# LED_Cube_8x8x8_Nano.net
KiCad netlist of a schematic drawn in EasyEDA
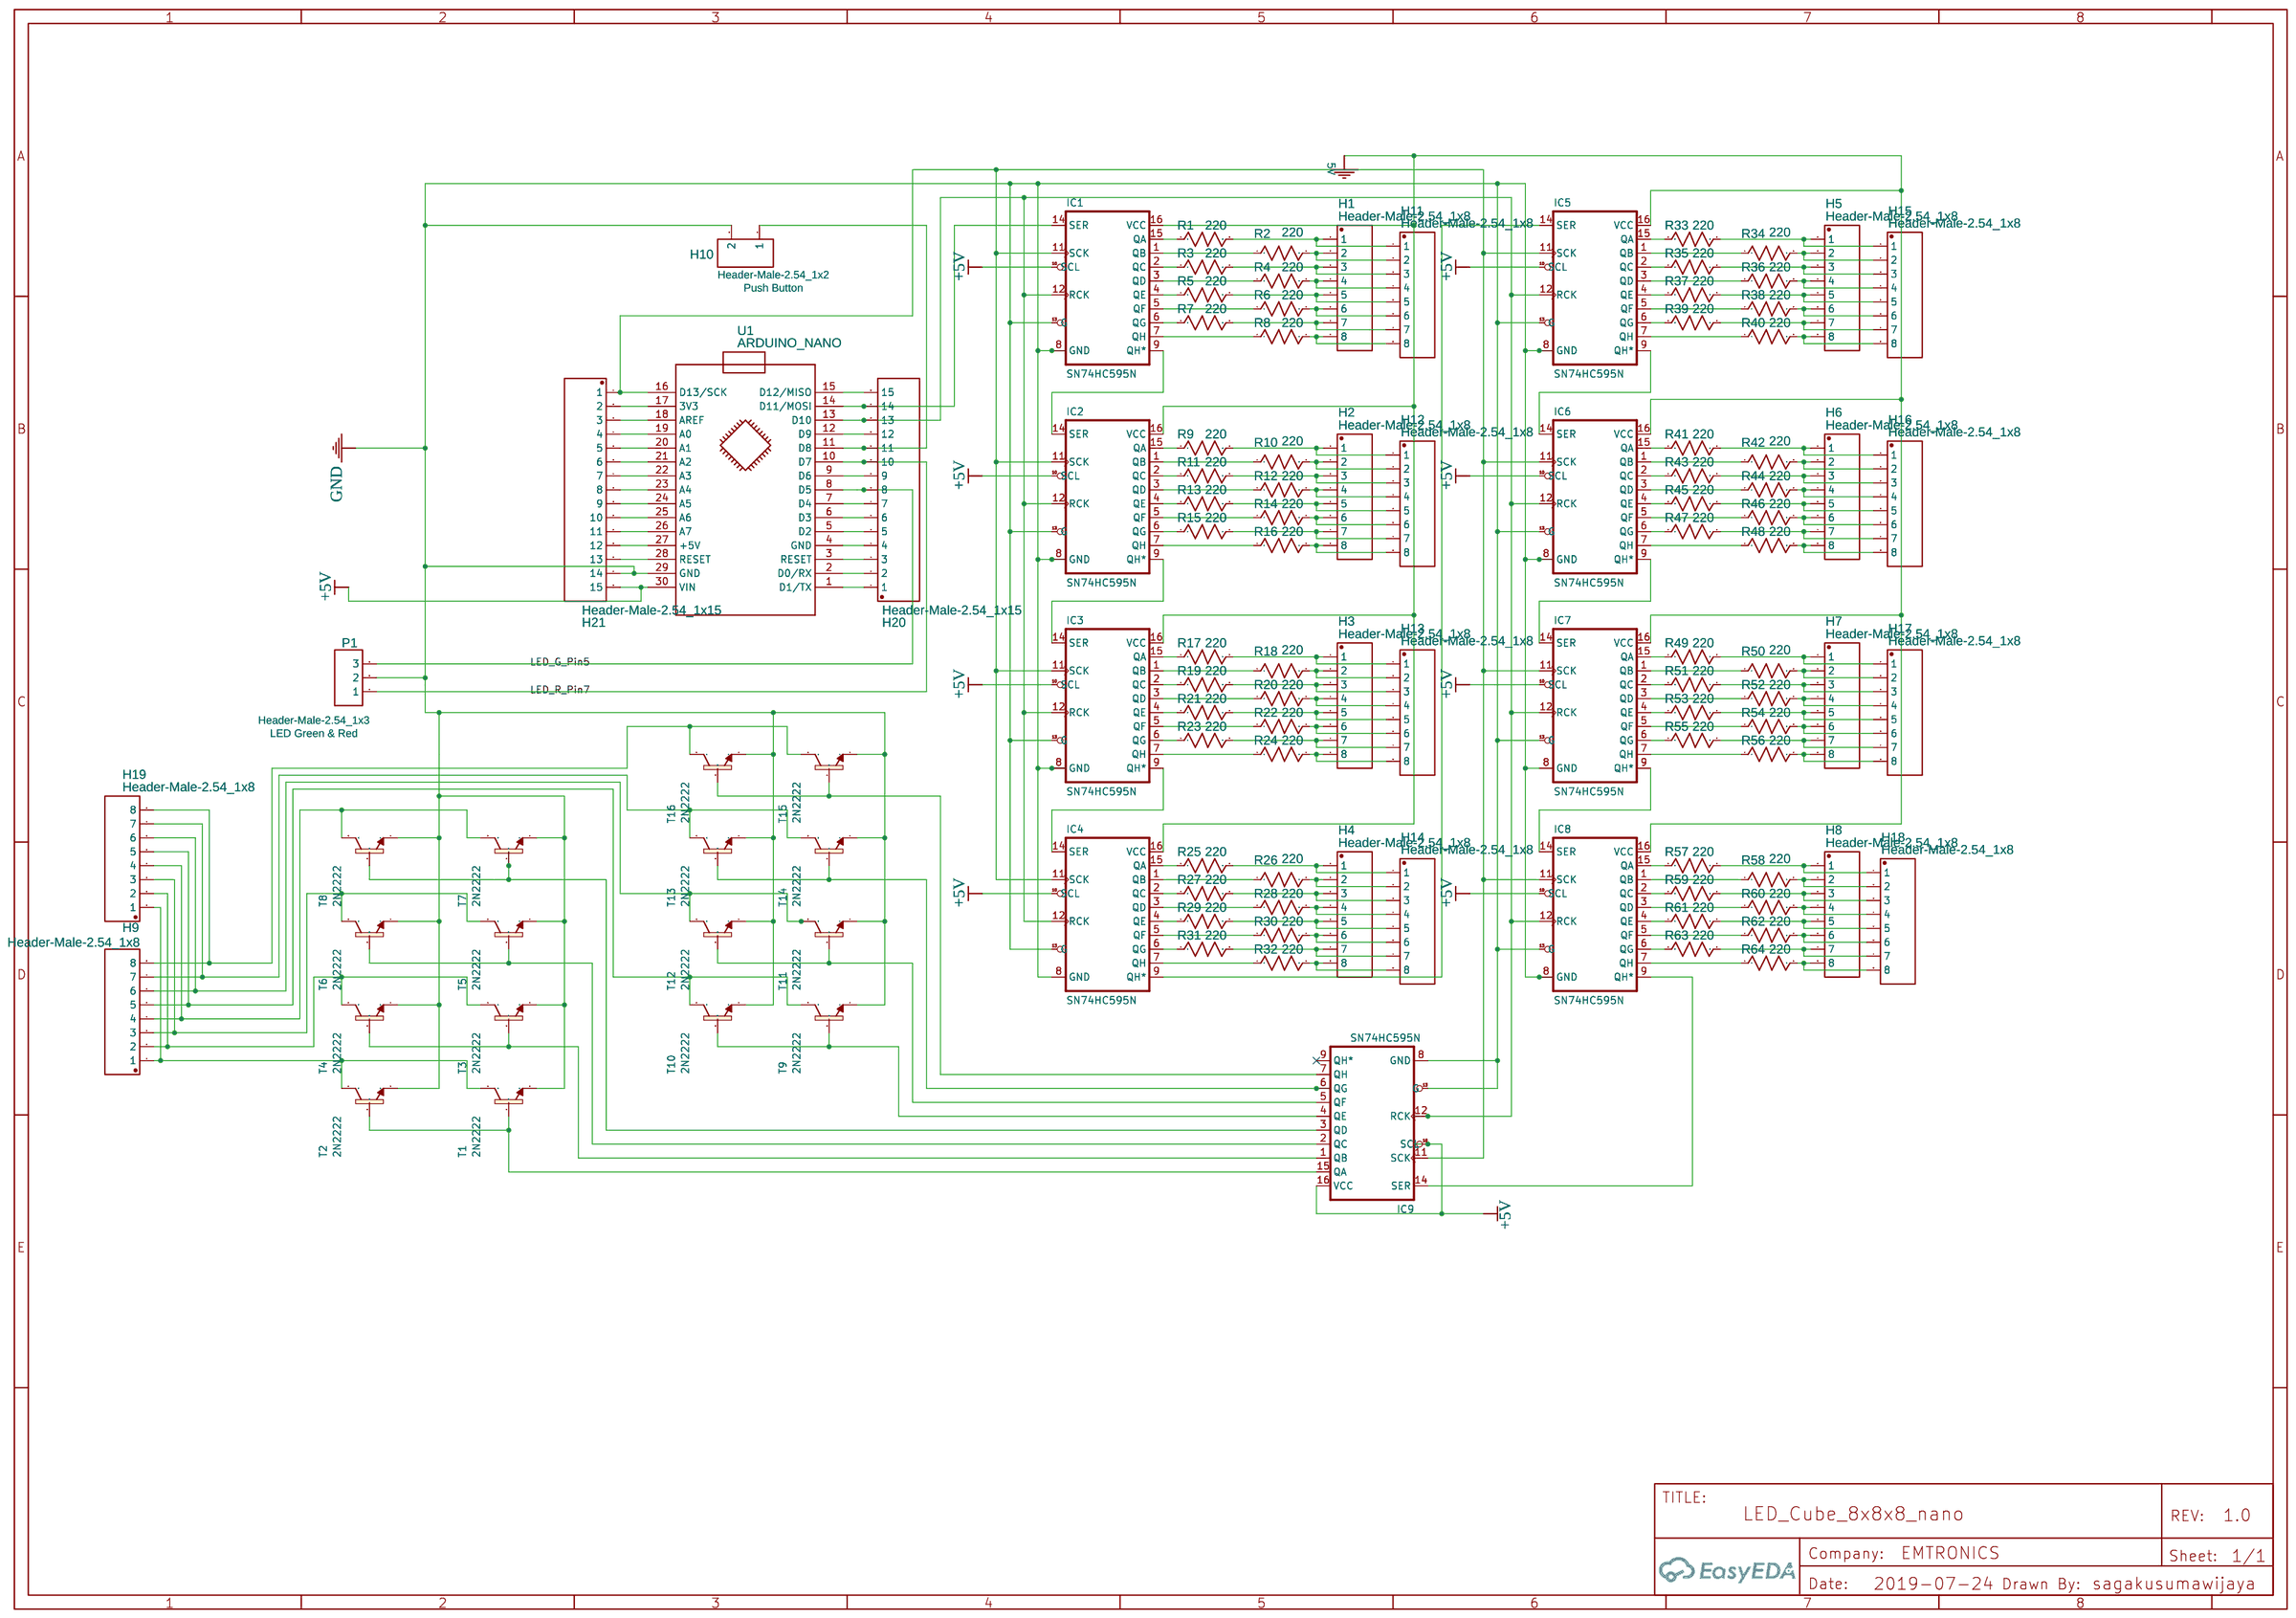
[diagram p0: schematic sheet]

(export (version "E")
  (design (tool "Eeschema 10.0.6"))
  (components
    (comp (ref "H1")
      (value "Header-Male-2.54_1x8")
      (fields
        (field (name "BOM_Manufacturer Part") "210S-1*8P L=11.6MMGold-plated black")
        (field (name "BOM_Supplier Part") "C124381")
      )
      (libsource (lib "") (part "Unknown_960_200"))
    )
    (comp (ref "H2")
      (value "Header-Male-2.54_1x8")
      (fields
        (field (name "BOM_Manufacturer Part") "210S-1*8P L=11.6MMGold-plated black")
        (field (name "BOM_Supplier Part") "C124381")
      )
      (libsource (lib "") (part "Unknown_960_350"))
    )
    (comp (ref "H3")
      (value "Header-Male-2.54_1x8")
      (fields
        (field (name "BOM_Manufacturer Part") "210S-1*8P L=11.6MMGold-plated black")
        (field (name "BOM_Supplier Part") "C124381")
      )
      (libsource (lib "") (part "Unknown_960_500"))
    )
    (comp (ref "H4")
      (value "Header-Male-2.54_1x8")
      (fields
        (field (name "BOM_Manufacturer Part") "210S-1*8P L=11.6MMGold-plated black")
        (field (name "BOM_Supplier Part") "C124381")
      )
      (libsource (lib "") (part "Unknown_960_650"))
    )
    (comp (ref "H5")
      (value "Header-Male-2.54_1x8")
      (fields
        (field (name "BOM_Manufacturer Part") "210S-1*8P L=11.6MMGold-plated black")
        (field (name "BOM_Supplier Part") "C124381")
      )
      (libsource (lib "") (part "Unknown_1310_200"))
    )
    (comp (ref "H6")
      (value "Header-Male-2.54_1x8")
      (fields
        (field (name "BOM_Manufacturer Part") "210S-1*8P L=11.6MMGold-plated black")
        (field (name "BOM_Supplier Part") "C124381")
      )
      (libsource (lib "") (part "Unknown_1310_350"))
    )
    (comp (ref "H7")
      (value "Header-Male-2.54_1x8")
      (fields
        (field (name "BOM_Manufacturer Part") "210S-1*8P L=11.6MMGold-plated black")
        (field (name "BOM_Supplier Part") "C124381")
      )
      (libsource (lib "") (part "Unknown_1310_500"))
    )
    (comp (ref "H8")
      (value "Header-Male-2.54_1x8")
      (fields
        (field (name "BOM_Manufacturer Part") "210S-1*8P L=11.6MMGold-plated black")
        (field (name "BOM_Supplier Part") "C124381")
      )
      (libsource (lib "") (part "Unknown_1310_650"))
    )
    (comp (ref "H9")
      (value "Header-Male-2.54_1x8")
      (fields
        (field (name "BOM_Manufacturer Part") "210S-1*8P L=11.6MMGold-plated black")
        (field (name "BOM_Supplier Part") "C124381")
      )
      (libsource (lib "") (part "Unknown_80_720"))
    )
    (comp (ref "H10")
      (value "Header-Male-2.54_1x2\\nPush Button")
      (fields (field (name "BOM_Manufacturer Part") "826629-2") (field (name "BOM_Supplier Part") "C86471"))
      (libsource (lib "") (part "Unknown_525_170"))
    )
    (comp (ref "H11")
      (value "Header-Male-2.54_1x8")
      (fields
        (field (name "BOM_Manufacturer Part") "210S-1*8P L=11.6MMGold-plated black")
        (field (name "BOM_Supplier Part") "C124381")
      )
      (libsource (lib "") (part "Unknown_1005_205"))
    )
    (comp (ref "H12")
      (value "Header-Male-2.54_1x8")
      (fields
        (field (name "BOM_Manufacturer Part") "210S-1*8P L=11.6MMGold-plated black")
        (field (name "BOM_Supplier Part") "C124381")
      )
      (libsource (lib "") (part "Unknown_1005_355"))
    )
    (comp (ref "H13")
      (value "Header-Male-2.54_1x8")
      (fields
        (field (name "BOM_Manufacturer Part") "210S-1*8P L=11.6MMGold-plated black")
        (field (name "BOM_Supplier Part") "C124381")
      )
      (libsource (lib "") (part "Unknown_1005_505"))
    )
    (comp (ref "H14")
      (value "Header-Male-2.54_1x8")
      (fields
        (field (name "BOM_Manufacturer Part") "210S-1*8P L=11.6MMGold-plated black")
        (field (name "BOM_Supplier Part") "C124381")
      )
      (libsource (lib "") (part "Unknown_1005_655"))
    )
    (comp (ref "H15")
      (value "Header-Male-2.54_1x8")
      (fields
        (field (name "BOM_Manufacturer Part") "210S-1*8P L=11.6MMGold-plated black")
        (field (name "BOM_Supplier Part") "C124381")
      )
      (libsource (lib "") (part "Unknown_1355_205"))
    )
    (comp (ref "H16")
      (value "Header-Male-2.54_1x8")
      (fields
        (field (name "BOM_Manufacturer Part") "210S-1*8P L=11.6MMGold-plated black")
        (field (name "BOM_Supplier Part") "C124381")
      )
      (libsource (lib "") (part "Unknown_1355_355"))
    )
    (comp (ref "H17")
      (value "Header-Male-2.54_1x8")
      (fields
        (field (name "BOM_Manufacturer Part") "210S-1*8P L=11.6MMGold-plated black")
        (field (name "BOM_Supplier Part") "C124381")
      )
      (libsource (lib "") (part "Unknown_1355_505"))
    )
    (comp (ref "H18")
      (value "Header-Male-2.54_1x8")
      (fields
        (field (name "BOM_Manufacturer Part") "210S-1*8P L=11.6MMGold-plated black")
        (field (name "BOM_Supplier Part") "C124381")
      )
      (libsource (lib "") (part "Unknown_1350_655"))
    )
    (comp (ref "H19")
      (value "Header-Male-2.54_1x8")
      (fields
        (field (name "BOM_Manufacturer Part") "210S-1*8P L=11.6MMGold-plated black")
        (field (name "BOM_Supplier Part") "C124381")
      )
      (libsource (lib "") (part "Unknown_80_610"))
    )
    (comp (ref "H20")
      (value "Header-Male-2.54_1x15")
      (fields
        (field (name "BOM_Manufacturer Part") "210S-1*15P L=11.6MMGold-plated black")
        (field (name "BOM_Supplier Part") "C124373")
      )
      (libsource (lib "") (part "Unknown_630_340"))
    )
    (comp (ref "H21")
      (value "Header-Male-2.54_1x15")
      (fields
        (field (name "BOM_Manufacturer Part") "210S-1*15P L=11.6MMGold-plated black")
        (field (name "BOM_Supplier Part") "C124373")
      )
      (libsource (lib "") (part "Unknown_415_350"))
    )
    (comp (ref "IC1") (value "SN74HC595N") (libsource (lib "") (part "Unknown_775_195")))
    (comp (ref "IC2") (value "SN74HC595N") (libsource (lib "") (part "Unknown_775_345")))
    (comp (ref "IC3") (value "SN74HC595N") (libsource (lib "") (part "Unknown_775_495")))
    (comp (ref "IC4") (value "SN74HC595N") (libsource (lib "") (part "Unknown_775_645")))
    (comp (ref "IC5") (value "SN74HC595N") (libsource (lib "") (part "Unknown_1125_195")))
    (comp (ref "IC6") (value "SN74HC595N") (libsource (lib "") (part "Unknown_1125_345")))
    (comp (ref "IC7") (value "SN74HC595N") (libsource (lib "") (part "Unknown_1125_495")))
    (comp (ref "IC8") (value "SN74HC595N") (libsource (lib "") (part "Unknown_1125_645")))
    (comp (ref "IC9") (value "SN74HC595N") (libsource (lib "") (part "Unknown_985_805")))
    (comp (ref "P1")
      (value "Header-Male-2.54_1x3\\nLED Green & Red")
      (fields
        (field (name "BOM_Manufacturer Part") "Header2.54mm 1*3P")
        (field (name "BOM_Supplier Part") "C49257")
      )
      (libsource (lib "") (part "Unknown_245_480"))
    )
    (comp (ref "R1")
      (value "220")
      (fields (field (name "BOM_Manufacturer Part") "?"))
      (libsource (lib "") (part "Res_AXIAL-0.4(1/4W)_US"))
    )
    (comp (ref "R2")
      (value "220")
      (fields (field (name "BOM_Manufacturer Part") "?"))
      (libsource (lib "") (part "Res_AXIAL-0.4(1/4W)_US"))
    )
    (comp (ref "R3")
      (value "220")
      (fields (field (name "BOM_Manufacturer Part") "?"))
      (libsource (lib "") (part "Res_AXIAL-0.4(1/4W)_US"))
    )
    (comp (ref "R4")
      (value "220")
      (fields (field (name "BOM_Manufacturer Part") "?"))
      (libsource (lib "") (part "Res_AXIAL-0.4(1/4W)_US"))
    )
    (comp (ref "R5")
      (value "220")
      (fields (field (name "BOM_Manufacturer Part") "?"))
      (libsource (lib "") (part "Res_AXIAL-0.4(1/4W)_US"))
    )
    (comp (ref "R6")
      (value "220")
      (fields (field (name "BOM_Manufacturer Part") "?"))
      (libsource (lib "") (part "Res_AXIAL-0.4(1/4W)_US"))
    )
    (comp (ref "R7")
      (value "220")
      (fields (field (name "BOM_Manufacturer Part") "?"))
      (libsource (lib "") (part "Res_AXIAL-0.4(1/4W)_US"))
    )
    (comp (ref "R8")
      (value "220")
      (fields (field (name "BOM_Manufacturer Part") "?"))
      (libsource (lib "") (part "Res_AXIAL-0.4(1/4W)_US"))
    )
    (comp (ref "R9")
      (value "220")
      (fields (field (name "BOM_Manufacturer Part") "?"))
      (libsource (lib "") (part "Res_AXIAL-0.4(1/4W)_US"))
    )
    (comp (ref "R10")
      (value "220")
      (fields (field (name "BOM_Manufacturer Part") "?"))
      (libsource (lib "") (part "Res_AXIAL-0.4(1/4W)_US"))
    )
    (comp (ref "R11")
      (value "220")
      (fields (field (name "BOM_Manufacturer Part") "?"))
      (libsource (lib "") (part "Res_AXIAL-0.4(1/4W)_US"))
    )
    (comp (ref "R12")
      (value "220")
      (fields (field (name "BOM_Manufacturer Part") "?"))
      (libsource (lib "") (part "Res_AXIAL-0.4(1/4W)_US"))
    )
    (comp (ref "R13")
      (value "220")
      (fields (field (name "BOM_Manufacturer Part") "?"))
      (libsource (lib "") (part "Res_AXIAL-0.4(1/4W)_US"))
    )
    (comp (ref "R14")
      (value "220")
      (fields (field (name "BOM_Manufacturer Part") "?"))
      (libsource (lib "") (part "Res_AXIAL-0.4(1/4W)_US"))
    )
    (comp (ref "R15")
      (value "220")
      (fields (field (name "BOM_Manufacturer Part") "?"))
      (libsource (lib "") (part "Res_AXIAL-0.4(1/4W)_US"))
    )
    (comp (ref "R16")
      (value "220")
      (fields (field (name "BOM_Manufacturer Part") "?"))
      (libsource (lib "") (part "Res_AXIAL-0.4(1/4W)_US"))
    )
    (comp (ref "R17")
      (value "220")
      (fields (field (name "BOM_Manufacturer Part") "?"))
      (libsource (lib "") (part "Res_AXIAL-0.4(1/4W)_US"))
    )
    (comp (ref "R18")
      (value "220")
      (fields (field (name "BOM_Manufacturer Part") "?"))
      (libsource (lib "") (part "Res_AXIAL-0.4(1/4W)_US"))
    )
    (comp (ref "R19")
      (value "220")
      (fields (field (name "BOM_Manufacturer Part") "?"))
      (libsource (lib "") (part "Res_AXIAL-0.4(1/4W)_US"))
    )
    (comp (ref "R20")
      (value "220")
      (fields (field (name "BOM_Manufacturer Part") "?"))
      (libsource (lib "") (part "Res_AXIAL-0.4(1/4W)_US"))
    )
    (comp (ref "R21")
      (value "220")
      (fields (field (name "BOM_Manufacturer Part") "?"))
      (libsource (lib "") (part "Res_AXIAL-0.4(1/4W)_US"))
    )
    (comp (ref "R22")
      (value "220")
      (fields (field (name "BOM_Manufacturer Part") "?"))
      (libsource (lib "") (part "Res_AXIAL-0.4(1/4W)_US"))
    )
    (comp (ref "R23")
      (value "220")
      (fields (field (name "BOM_Manufacturer Part") "?"))
      (libsource (lib "") (part "Res_AXIAL-0.4(1/4W)_US"))
    )
    (comp (ref "R24")
      (value "220")
      (fields (field (name "BOM_Manufacturer Part") "?"))
      (libsource (lib "") (part "Res_AXIAL-0.4(1/4W)_US"))
    )
    (comp (ref "R25")
      (value "220")
      (fields (field (name "BOM_Manufacturer Part") "?"))
      (libsource (lib "") (part "Res_AXIAL-0.4(1/4W)_US"))
    )
    (comp (ref "R26")
      (value "220")
      (fields (field (name "BOM_Manufacturer Part") "?"))
      (libsource (lib "") (part "Res_AXIAL-0.4(1/4W)_US"))
    )
    (comp (ref "R27")
      (value "220")
      (fields (field (name "BOM_Manufacturer Part") "?"))
      (libsource (lib "") (part "Res_AXIAL-0.4(1/4W)_US"))
    )
    (comp (ref "R28")
      (value "220")
      (fields (field (name "BOM_Manufacturer Part") "?"))
      (libsource (lib "") (part "Res_AXIAL-0.4(1/4W)_US"))
    )
    (comp (ref "R29")
      (value "220")
      (fields (field (name "BOM_Manufacturer Part") "?"))
      (libsource (lib "") (part "Res_AXIAL-0.4(1/4W)_US"))
    )
    (comp (ref "R30")
      (value "220")
      (fields (field (name "BOM_Manufacturer Part") "?"))
      (libsource (lib "") (part "Res_AXIAL-0.4(1/4W)_US"))
    )
    (comp (ref "R31")
      (value "220")
      (fields (field (name "BOM_Manufacturer Part") "?"))
      (libsource (lib "") (part "Res_AXIAL-0.4(1/4W)_US"))
    )
    (comp (ref "R32")
      (value "220")
      (fields (field (name "BOM_Manufacturer Part") "?"))
      (libsource (lib "") (part "Res_AXIAL-0.4(1/4W)_US"))
    )
    (comp (ref "R33")
      (value "220")
      (fields (field (name "BOM_Manufacturer Part") "?"))
      (libsource (lib "") (part "Res_AXIAL-0.4(1/4W)_US"))
    )
    (comp (ref "R34")
      (value "220")
      (fields (field (name "BOM_Manufacturer Part") "?"))
      (libsource (lib "") (part "Res_AXIAL-0.4(1/4W)_US"))
    )
    (comp (ref "R35")
      (value "220")
      (fields (field (name "BOM_Manufacturer Part") "?"))
      (libsource (lib "") (part "Res_AXIAL-0.4(1/4W)_US"))
    )
    (comp (ref "R36")
      (value "220")
      (fields (field (name "BOM_Manufacturer Part") "?"))
      (libsource (lib "") (part "Res_AXIAL-0.4(1/4W)_US"))
    )
    (comp (ref "R37")
      (value "220")
      (fields (field (name "BOM_Manufacturer Part") "?"))
      (libsource (lib "") (part "Res_AXIAL-0.4(1/4W)_US"))
    )
    (comp (ref "R38")
      (value "220")
      (fields (field (name "BOM_Manufacturer Part") "?"))
      (libsource (lib "") (part "Res_AXIAL-0.4(1/4W)_US"))
    )
    (comp (ref "R39")
      (value "220")
      (fields (field (name "BOM_Manufacturer Part") "?"))
      (libsource (lib "") (part "Res_AXIAL-0.4(1/4W)_US"))
    )
    (comp (ref "R40")
      (value "220")
      (fields (field (name "BOM_Manufacturer Part") "?"))
      (libsource (lib "") (part "Res_AXIAL-0.4(1/4W)_US"))
    )
    (comp (ref "R41")
      (value "220")
      (fields (field (name "BOM_Manufacturer Part") "?"))
      (libsource (lib "") (part "Res_AXIAL-0.4(1/4W)_US"))
    )
    (comp (ref "R42")
      (value "220")
      (fields (field (name "BOM_Manufacturer Part") "?"))
      (libsource (lib "") (part "Res_AXIAL-0.4(1/4W)_US"))
    )
    (comp (ref "R43")
      (value "220")
      (fields (field (name "BOM_Manufacturer Part") "?"))
      (libsource (lib "") (part "Res_AXIAL-0.4(1/4W)_US"))
    )
    (comp (ref "R44")
      (value "220")
      (fields (field (name "BOM_Manufacturer Part") "?"))
      (libsource (lib "") (part "Res_AXIAL-0.4(1/4W)_US"))
    )
    (comp (ref "R45")
      (value "220")
      (fields (field (name "BOM_Manufacturer Part") "?"))
      (libsource (lib "") (part "Res_AXIAL-0.4(1/4W)_US"))
    )
    (comp (ref "R46")
      (value "220")
      (fields (field (name "BOM_Manufacturer Part") "?"))
      (libsource (lib "") (part "Res_AXIAL-0.4(1/4W)_US"))
    )
    (comp (ref "R47")
      (value "220")
      (fields (field (name "BOM_Manufacturer Part") "?"))
      (libsource (lib "") (part "Res_AXIAL-0.4(1/4W)_US"))
    )
    (comp (ref "R48")
      (value "220")
      (fields (field (name "BOM_Manufacturer Part") "?"))
      (libsource (lib "") (part "Res_AXIAL-0.4(1/4W)_US"))
    )
    (comp (ref "R49")
      (value "220")
      (fields (field (name "BOM_Manufacturer Part") "?"))
      (libsource (lib "") (part "Res_AXIAL-0.4(1/4W)_US"))
    )
    (comp (ref "R50")
      (value "220")
      (fields (field (name "BOM_Manufacturer Part") "?"))
      (libsource (lib "") (part "Res_AXIAL-0.4(1/4W)_US"))
    )
    (comp (ref "R51")
      (value "220")
      (fields (field (name "BOM_Manufacturer Part") "?"))
      (libsource (lib "") (part "Res_AXIAL-0.4(1/4W)_US"))
    )
    (comp (ref "R52")
      (value "220")
      (fields (field (name "BOM_Manufacturer Part") "?"))
      (libsource (lib "") (part "Res_AXIAL-0.4(1/4W)_US"))
    )
    (comp (ref "R53")
      (value "220")
      (fields (field (name "BOM_Manufacturer Part") "?"))
      (libsource (lib "") (part "Res_AXIAL-0.4(1/4W)_US"))
    )
    (comp (ref "R54")
      (value "220")
      (fields (field (name "BOM_Manufacturer Part") "?"))
      (libsource (lib "") (part "Res_AXIAL-0.4(1/4W)_US"))
    )
    (comp (ref "R55")
      (value "220")
      (fields (field (name "BOM_Manufacturer Part") "?"))
      (libsource (lib "") (part "Res_AXIAL-0.4(1/4W)_US"))
    )
    (comp (ref "R56")
      (value "220")
      (fields (field (name "BOM_Manufacturer Part") "?"))
      (libsource (lib "") (part "Res_AXIAL-0.4(1/4W)_US"))
    )
    (comp (ref "R57")
      (value "220")
      (fields (field (name "BOM_Manufacturer Part") "?"))
      (libsource (lib "") (part "Res_AXIAL-0.4(1/4W)_US"))
    )
    (comp (ref "R58")
      (value "220")
      (fields (field (name "BOM_Manufacturer Part") "?"))
      (libsource (lib "") (part "Res_AXIAL-0.4(1/4W)_US"))
    )
    (comp (ref "R59")
      (value "220")
      (fields (field (name "BOM_Manufacturer Part") "?"))
      (libsource (lib "") (part "Res_AXIAL-0.4(1/4W)_US"))
    )
    (comp (ref "R60")
      (value "220")
      (fields (field (name "BOM_Manufacturer Part") "?"))
      (libsource (lib "") (part "Res_AXIAL-0.4(1/4W)_US"))
    )
    (comp (ref "R61")
      (value "220")
      (fields (field (name "BOM_Manufacturer Part") "?"))
      (libsource (lib "") (part "Res_AXIAL-0.4(1/4W)_US"))
    )
    (comp (ref "R62")
      (value "220")
      (fields (field (name "BOM_Manufacturer Part") "?"))
      (libsource (lib "") (part "Res_AXIAL-0.4(1/4W)_US"))
    )
    (comp (ref "R63")
      (value "220")
      (fields (field (name "BOM_Manufacturer Part") "?"))
      (libsource (lib "") (part "Res_AXIAL-0.4(1/4W)_US"))
    )
    (comp (ref "R64")
      (value "220")
      (fields (field (name "BOM_Manufacturer Part") "?"))
      (libsource (lib "") (part "Res_AXIAL-0.4(1/4W)_US"))
    )
    (comp (ref "T1") (value "2N2222") (libsource (lib "") (part "Unknown_355_785")))
    (comp (ref "T2") (value "2N2222") (libsource (lib "") (part "Unknown_255_785")))
    (comp (ref "T3") (value "2N2222") (libsource (lib "") (part "Unknown_355_725")))
    (comp (ref "T4") (value "2N2222") (libsource (lib "") (part "Unknown_255_725")))
    (comp (ref "T5") (value "2N2222") (libsource (lib "") (part "Unknown_355_665")))
    (comp (ref "T6") (value "2N2222") (libsource (lib "") (part "Unknown_255_665")))
    (comp (ref "T7") (value "2N2222") (libsource (lib "") (part "Unknown_355_605")))
    (comp (ref "T8") (value "2N2222") (libsource (lib "") (part "Unknown_255_605")))
    (comp (ref "T9") (value "2N2222") (libsource (lib "") (part "Unknown_585_725")))
    (comp (ref "T10") (value "2N2222") (libsource (lib "") (part "Unknown_505_725")))
    (comp (ref "T11") (value "2N2222") (libsource (lib "") (part "Unknown_585_665")))
    (comp (ref "T12") (value "2N2222") (libsource (lib "") (part "Unknown_505_665")))
    (comp (ref "T13") (value "2N2222") (libsource (lib "") (part "Unknown_505_605")))
    (comp (ref "T14") (value "2N2222") (libsource (lib "") (part "Unknown_585_605")))
    (comp (ref "T15") (value "2N2222") (libsource (lib "") (part "Unknown_585_545")))
    (comp (ref "T16") (value "2N2222") (libsource (lib "") (part "Unknown_505_545")))
    (comp (ref "U1")
      (value "ARDUINO_NANO")
      (fields (field (name "BOM_Manufacturer Part") "?"))
      (libsource (lib "") (part "Unknown_525_340"))
    )
  )
  (nets
    (net (code "1") (name "+5V") (class "Default")
      (node (ref "H21") (pin "15") (pinfunction "15_15") (pintype "unspecified"))
      (node (ref "IC1") (pin "10") (pinfunction "SCL_10") (pintype "bidirectional"))
      (node (ref "IC2") (pin "10") (pinfunction "SCL_10") (pintype "bidirectional"))
      (node (ref "IC3") (pin "10") (pinfunction "SCL_10") (pintype "bidirectional"))
      (node (ref "IC4") (pin "10") (pinfunction "SCL_10") (pintype "bidirectional"))
      (node (ref "IC5") (pin "10") (pinfunction "SCL_10") (pintype "bidirectional"))
      (node (ref "IC6") (pin "10") (pinfunction "SCL_10") (pintype "bidirectional"))
      (node (ref "IC7") (pin "10") (pinfunction "SCL_10") (pintype "bidirectional"))
      (node (ref "IC8") (pin "10") (pinfunction "SCL_10") (pintype "bidirectional"))
      (node (ref "IC9") (pin "10") (pinfunction "SCL_10") (pintype "bidirectional"))
      (node (ref "IC9") (pin "16") (pinfunction "VCC_16") (pintype "bidirectional"))
      (node (ref "U1") (pin "30") (pinfunction "VIN_30") (pintype "unspecified"))
    )
    (net (code "2") (name "/LED_G_Pin5") (class "Default")
      (node (ref "H20") (pin "8") (pinfunction "8_8") (pintype "unspecified"))
      (node (ref "P1") (pin "3") (pinfunction "3_3") (pintype "input"))
      (node (ref "U1") (pin "8") (pinfunction "D5_8") (pintype "unspecified"))
    )
    (net (code "3") (name "/LED_R_Pin7") (class "Default")
      (node (ref "H20") (pin "10") (pinfunction "10_10") (pintype "unspecified"))
      (node (ref "P1") (pin "1") (pinfunction "1_1") (pintype "input"))
      (node (ref "U1") (pin "10") (pinfunction "D7_10") (pintype "unspecified"))
    )
    (net (code "4") (name "5V") (class "Default")
      (node (ref "IC1") (pin "16") (pinfunction "VCC_16") (pintype "bidirectional"))
      (node (ref "IC2") (pin "16") (pinfunction "VCC_16") (pintype "bidirectional"))
      (node (ref "IC3") (pin "16") (pinfunction "VCC_16") (pintype "bidirectional"))
      (node (ref "IC4") (pin "16") (pinfunction "VCC_16") (pintype "bidirectional"))
      (node (ref "IC5") (pin "16") (pinfunction "VCC_16") (pintype "bidirectional"))
      (node (ref "IC6") (pin "16") (pinfunction "VCC_16") (pintype "bidirectional"))
      (node (ref "IC7") (pin "16") (pinfunction "VCC_16") (pintype "bidirectional"))
      (node (ref "IC8") (pin "16") (pinfunction "VCC_16") (pintype "bidirectional"))
    )
    (net (code "5") (name "GND") (class "Default")
      (node (ref "H10") (pin "2") (pinfunction "2_2") (pintype "unspecified"))
      (node (ref "H21") (pin "14") (pinfunction "14_14") (pintype "unspecified"))
      (node (ref "IC1") (pin "13") (pinfunction "G_13") (pintype "bidirectional"))
      (node (ref "IC1") (pin "8") (pinfunction "GND_8") (pintype "bidirectional"))
      (node (ref "IC2") (pin "13") (pinfunction "G_13") (pintype "bidirectional"))
      (node (ref "IC2") (pin "8") (pinfunction "GND_8") (pintype "bidirectional"))
      (node (ref "IC3") (pin "13") (pinfunction "G_13") (pintype "bidirectional"))
      (node (ref "IC3") (pin "8") (pinfunction "GND_8") (pintype "bidirectional"))
      (node (ref "IC4") (pin "13") (pinfunction "G_13") (pintype "bidirectional"))
      (node (ref "IC4") (pin "8") (pinfunction "GND_8") (pintype "bidirectional"))
      (node (ref "IC5") (pin "13") (pinfunction "G_13") (pintype "bidirectional"))
      (node (ref "IC5") (pin "8") (pinfunction "GND_8") (pintype "bidirectional"))
      (node (ref "IC6") (pin "13") (pinfunction "G_13") (pintype "bidirectional"))
      (node (ref "IC6") (pin "8") (pinfunction "GND_8") (pintype "bidirectional"))
      (node (ref "IC7") (pin "13") (pinfunction "G_13") (pintype "bidirectional"))
      (node (ref "IC7") (pin "8") (pinfunction "GND_8") (pintype "bidirectional"))
      (node (ref "IC8") (pin "13") (pinfunction "G_13") (pintype "bidirectional"))
      (node (ref "IC8") (pin "8") (pinfunction "GND_8") (pintype "bidirectional"))
      (node (ref "IC9") (pin "13") (pinfunction "G_13") (pintype "bidirectional"))
      (node (ref "IC9") (pin "8") (pinfunction "GND_8") (pintype "bidirectional"))
      (node (ref "P1") (pin "2") (pinfunction "2_2") (pintype "input"))
      (node (ref "T1") (pin "E") (pinfunction "E_E") (pintype "bidirectional"))
      (node (ref "T10") (pin "E") (pinfunction "E_E") (pintype "bidirectional"))
      (node (ref "T11") (pin "E") (pinfunction "E_E") (pintype "bidirectional"))
      (node (ref "T12") (pin "E") (pinfunction "E_E") (pintype "bidirectional"))
      (node (ref "T13") (pin "E") (pinfunction "E_E") (pintype "bidirectional"))
      (node (ref "T14") (pin "E") (pinfunction "E_E") (pintype "bidirectional"))
      (node (ref "T15") (pin "E") (pinfunction "E_E") (pintype "bidirectional"))
      (node (ref "T16") (pin "E") (pinfunction "E_E") (pintype "bidirectional"))
      (node (ref "T2") (pin "E") (pinfunction "E_E") (pintype "bidirectional"))
      (node (ref "T3") (pin "E") (pinfunction "E_E") (pintype "bidirectional"))
      (node (ref "T4") (pin "E") (pinfunction "E_E") (pintype "bidirectional"))
      (node (ref "T5") (pin "E") (pinfunction "E_E") (pintype "bidirectional"))
      (node (ref "T6") (pin "E") (pinfunction "E_E") (pintype "bidirectional"))
      (node (ref "T7") (pin "E") (pinfunction "E_E") (pintype "bidirectional"))
      (node (ref "T8") (pin "E") (pinfunction "E_E") (pintype "bidirectional"))
      (node (ref "T9") (pin "E") (pinfunction "E_E") (pintype "bidirectional"))
      (node (ref "U1") (pin "29") (pinfunction "GND_29") (pintype "unspecified"))
    )
    (net (code "6") (name "Net-(H1-Pad1)") (class "Default")
      (node (ref "H1") (pin "1") (pinfunction "1_1") (pintype "unspecified"))
      (node (ref "H11") (pin "1") (pinfunction "1_1") (pintype "unspecified"))
      (node (ref "R1") (pin "2") (pinfunction "2_2") (pintype "unspecified"))
    )
    (net (code "7") (name "Net-(H1-Pad2)") (class "Default")
      (node (ref "H1") (pin "2") (pinfunction "2_2") (pintype "unspecified"))
      (node (ref "H11") (pin "2") (pinfunction "2_2") (pintype "unspecified"))
      (node (ref "R2") (pin "2") (pinfunction "2_2") (pintype "unspecified"))
    )
    (net (code "8") (name "Net-(H1-Pad3)") (class "Default")
      (node (ref "H1") (pin "3") (pinfunction "3_3") (pintype "unspecified"))
      (node (ref "H11") (pin "3") (pinfunction "3_3") (pintype "unspecified"))
      (node (ref "R3") (pin "2") (pinfunction "2_2") (pintype "unspecified"))
    )
    (net (code "9") (name "Net-(H1-Pad4)") (class "Default")
      (node (ref "H1") (pin "4") (pinfunction "4_4") (pintype "unspecified"))
      (node (ref "H11") (pin "4") (pinfunction "4_4") (pintype "unspecified"))
      (node (ref "R4") (pin "2") (pinfunction "2_2") (pintype "unspecified"))
    )
    (net (code "10") (name "Net-(H1-Pad5)") (class "Default")
      (node (ref "H1") (pin "5") (pinfunction "5_5") (pintype "unspecified"))
      (node (ref "H11") (pin "5") (pinfunction "5_5") (pintype "unspecified"))
      (node (ref "R5") (pin "2") (pinfunction "2_2") (pintype "unspecified"))
    )
    (net (code "11") (name "Net-(H1-Pad6)") (class "Default")
      (node (ref "H1") (pin "6") (pinfunction "6_6") (pintype "unspecified"))
      (node (ref "H11") (pin "6") (pinfunction "6_6") (pintype "unspecified"))
      (node (ref "R6") (pin "2") (pinfunction "2_2") (pintype "unspecified"))
    )
    (net (code "12") (name "Net-(H1-Pad7)") (class "Default")
      (node (ref "H1") (pin "7") (pinfunction "7_7") (pintype "unspecified"))
      (node (ref "H11") (pin "7") (pinfunction "7_7") (pintype "unspecified"))
      (node (ref "R7") (pin "2") (pinfunction "2_2") (pintype "unspecified"))
    )
    (net (code "13") (name "Net-(H1-Pad8)") (class "Default")
      (node (ref "H1") (pin "8") (pinfunction "8_8") (pintype "unspecified"))
      (node (ref "H11") (pin "8") (pinfunction "8_8") (pintype "unspecified"))
      (node (ref "R8") (pin "2") (pinfunction "2_2") (pintype "unspecified"))
    )
    (net (code "14") (name "Net-(H12-Pad1)") (class "Default")
      (node (ref "H12") (pin "1") (pinfunction "1_1") (pintype "unspecified"))
      (node (ref "H2") (pin "1") (pinfunction "1_1") (pintype "unspecified"))
      (node (ref "R9") (pin "2") (pinfunction "2_2") (pintype "unspecified"))
    )
    (net (code "15") (name "Net-(H12-Pad2)") (class "Default")
      (node (ref "H12") (pin "2") (pinfunction "2_2") (pintype "unspecified"))
      (node (ref "H2") (pin "2") (pinfunction "2_2") (pintype "unspecified"))
      (node (ref "R10") (pin "2") (pinfunction "2_2") (pintype "unspecified"))
    )
    (net (code "16") (name "Net-(H12-Pad3)") (class "Default")
      (node (ref "H12") (pin "3") (pinfunction "3_3") (pintype "unspecified"))
      (node (ref "H2") (pin "3") (pinfunction "3_3") (pintype "unspecified"))
      (node (ref "R11") (pin "2") (pinfunction "2_2") (pintype "unspecified"))
    )
    (net (code "17") (name "Net-(H12-Pad4)") (class "Default")
      (node (ref "H12") (pin "4") (pinfunction "4_4") (pintype "unspecified"))
      (node (ref "H2") (pin "4") (pinfunction "4_4") (pintype "unspecified"))
      (node (ref "R12") (pin "2") (pinfunction "2_2") (pintype "unspecified"))
    )
    (net (code "18") (name "Net-(H12-Pad5)") (class "Default")
      (node (ref "H12") (pin "5") (pinfunction "5_5") (pintype "unspecified"))
      (node (ref "H2") (pin "5") (pinfunction "5_5") (pintype "unspecified"))
      (node (ref "R13") (pin "2") (pinfunction "2_2") (pintype "unspecified"))
    )
    (net (code "19") (name "Net-(H12-Pad6)") (class "Default")
      (node (ref "H12") (pin "6") (pinfunction "6_6") (pintype "unspecified"))
      (node (ref "H2") (pin "6") (pinfunction "6_6") (pintype "unspecified"))
      (node (ref "R14") (pin "2") (pinfunction "2_2") (pintype "unspecified"))
    )
    (net (code "20") (name "Net-(H12-Pad7)") (class "Default")
      (node (ref "H12") (pin "7") (pinfunction "7_7") (pintype "unspecified"))
      (node (ref "H2") (pin "7") (pinfunction "7_7") (pintype "unspecified"))
      (node (ref "R15") (pin "2") (pinfunction "2_2") (pintype "unspecified"))
    )
    (net (code "21") (name "Net-(H12-Pad8)") (class "Default")
      (node (ref "H12") (pin "8") (pinfunction "8_8") (pintype "unspecified"))
      (node (ref "H2") (pin "8") (pinfunction "8_8") (pintype "unspecified"))
      (node (ref "R16") (pin "2") (pinfunction "2_2") (pintype "unspecified"))
    )
    (net (code "22") (name "Net-(H13-Pad1)") (class "Default")
      (node (ref "H13") (pin "1") (pinfunction "1_1") (pintype "unspecified"))
      (node (ref "H3") (pin "1") (pinfunction "1_1") (pintype "unspecified"))
      (node (ref "R17") (pin "2") (pinfunction "2_2") (pintype "unspecified"))
    )
    (net (code "23") (name "Net-(H13-Pad2)") (class "Default")
      (node (ref "H13") (pin "2") (pinfunction "2_2") (pintype "unspecified"))
      (node (ref "H3") (pin "2") (pinfunction "2_2") (pintype "unspecified"))
      (node (ref "R18") (pin "2") (pinfunction "2_2") (pintype "unspecified"))
    )
    (net (code "24") (name "Net-(H13-Pad3)") (class "Default")
      (node (ref "H13") (pin "3") (pinfunction "3_3") (pintype "unspecified"))
      (node (ref "H3") (pin "3") (pinfunction "3_3") (pintype "unspecified"))
      (node (ref "R19") (pin "2") (pinfunction "2_2") (pintype "unspecified"))
    )
    (net (code "25") (name "Net-(H13-Pad4)") (class "Default")
      (node (ref "H13") (pin "4") (pinfunction "4_4") (pintype "unspecified"))
      (node (ref "H3") (pin "4") (pinfunction "4_4") (pintype "unspecified"))
      (node (ref "R20") (pin "2") (pinfunction "2_2") (pintype "unspecified"))
    )
    (net (code "26") (name "Net-(H13-Pad5)") (class "Default")
      (node (ref "H13") (pin "5") (pinfunction "5_5") (pintype "unspecified"))
      (node (ref "H3") (pin "5") (pinfunction "5_5") (pintype "unspecified"))
      (node (ref "R21") (pin "2") (pinfunction "2_2") (pintype "unspecified"))
    )
    (net (code "27") (name "Net-(H13-Pad6)") (class "Default")
      (node (ref "H13") (pin "6") (pinfunction "6_6") (pintype "unspecified"))
      (node (ref "H3") (pin "6") (pinfunction "6_6") (pintype "unspecified"))
      (node (ref "R22") (pin "2") (pinfunction "2_2") (pintype "unspecified"))
    )
    (net (code "28") (name "Net-(H13-Pad7)") (class "Default")
      (node (ref "H13") (pin "7") (pinfunction "7_7") (pintype "unspecified"))
      (node (ref "H3") (pin "7") (pinfunction "7_7") (pintype "unspecified"))
      (node (ref "R23") (pin "2") (pinfunction "2_2") (pintype "unspecified"))
    )
    (net (code "29") (name "Net-(H13-Pad8)") (class "Default")
      (node (ref "H13") (pin "8") (pinfunction "8_8") (pintype "unspecified"))
      (node (ref "H3") (pin "8") (pinfunction "8_8") (pintype "unspecified"))
      (node (ref "R24") (pin "2") (pinfunction "2_2") (pintype "unspecified"))
    )
    (net (code "30") (name "Net-(H14-Pad1)") (class "Default")
      (node (ref "H14") (pin "1") (pinfunction "1_1") (pintype "unspecified"))
      (node (ref "H4") (pin "1") (pinfunction "1_1") (pintype "unspecified"))
      (node (ref "R25") (pin "2") (pinfunction "2_2") (pintype "unspecified"))
    )
    (net (code "31") (name "Net-(H14-Pad2)") (class "Default")
      (node (ref "H14") (pin "2") (pinfunction "2_2") (pintype "unspecified"))
      (node (ref "H4") (pin "2") (pinfunction "2_2") (pintype "unspecified"))
      (node (ref "R26") (pin "2") (pinfunction "2_2") (pintype "unspecified"))
    )
    (net (code "32") (name "Net-(H14-Pad3)") (class "Default")
      (node (ref "H14") (pin "3") (pinfunction "3_3") (pintype "unspecified"))
      (node (ref "H4") (pin "3") (pinfunction "3_3") (pintype "unspecified"))
      (node (ref "R27") (pin "2") (pinfunction "2_2") (pintype "unspecified"))
    )
    (net (code "33") (name "Net-(H14-Pad4)") (class "Default")
      (node (ref "H14") (pin "4") (pinfunction "4_4") (pintype "unspecified"))
      (node (ref "H4") (pin "4") (pinfunction "4_4") (pintype "unspecified"))
      (node (ref "R28") (pin "2") (pinfunction "2_2") (pintype "unspecified"))
    )
    (net (code "34") (name "Net-(H14-Pad5)") (class "Default")
      (node (ref "H14") (pin "5") (pinfunction "5_5") (pintype "unspecified"))
      (node (ref "H4") (pin "5") (pinfunction "5_5") (pintype "unspecified"))
      (node (ref "R29") (pin "2") (pinfunction "2_2") (pintype "unspecified"))
    )
    (net (code "35") (name "Net-(H14-Pad6)") (class "Default")
      (node (ref "H14") (pin "6") (pinfunction "6_6") (pintype "unspecified"))
      (node (ref "H4") (pin "6") (pinfunction "6_6") (pintype "unspecified"))
      (node (ref "R30") (pin "2") (pinfunction "2_2") (pintype "unspecified"))
    )
    (net (code "36") (name "Net-(H14-Pad7)") (class "Default")
      (node (ref "H14") (pin "7") (pinfunction "7_7") (pintype "unspecified"))
      (node (ref "H4") (pin "7") (pinfunction "7_7") (pintype "unspecified"))
      (node (ref "R31") (pin "2") (pinfunction "2_2") (pintype "unspecified"))
    )
    (net (code "37") (name "Net-(H14-Pad8)") (class "Default")
      (node (ref "H14") (pin "8") (pinfunction "8_8") (pintype "unspecified"))
      (node (ref "H4") (pin "8") (pinfunction "8_8") (pintype "unspecified"))
      (node (ref "R32") (pin "2") (pinfunction "2_2") (pintype "unspecified"))
    )
    (net (code "38") (name "Net-(H15-Pad1)") (class "Default")
      (node (ref "H15") (pin "1") (pinfunction "1_1") (pintype "unspecified"))
      (node (ref "H5") (pin "1") (pinfunction "1_1") (pintype "unspecified"))
      (node (ref "R33") (pin "2") (pinfunction "2_2") (pintype "unspecified"))
    )
    (net (code "39") (name "Net-(H15-Pad2)") (class "Default")
      (node (ref "H15") (pin "2") (pinfunction "2_2") (pintype "unspecified"))
      (node (ref "H5") (pin "2") (pinfunction "2_2") (pintype "unspecified"))
      (node (ref "R34") (pin "2") (pinfunction "2_2") (pintype "unspecified"))
    )
    (net (code "40") (name "Net-(H15-Pad3)") (class "Default")
      (node (ref "H15") (pin "3") (pinfunction "3_3") (pintype "unspecified"))
      (node (ref "H5") (pin "3") (pinfunction "3_3") (pintype "unspecified"))
      (node (ref "R35") (pin "2") (pinfunction "2_2") (pintype "unspecified"))
    )
    (net (code "41") (name "Net-(H15-Pad4)") (class "Default")
      (node (ref "H15") (pin "4") (pinfunction "4_4") (pintype "unspecified"))
      (node (ref "H5") (pin "4") (pinfunction "4_4") (pintype "unspecified"))
      (node (ref "R36") (pin "2") (pinfunction "2_2") (pintype "unspecified"))
    )
    (net (code "42") (name "Net-(H15-Pad5)") (class "Default")
      (node (ref "H15") (pin "5") (pinfunction "5_5") (pintype "unspecified"))
      (node (ref "H5") (pin "5") (pinfunction "5_5") (pintype "unspecified"))
      (node (ref "R37") (pin "2") (pinfunction "2_2") (pintype "unspecified"))
    )
    (net (code "43") (name "Net-(H15-Pad6)") (class "Default")
      (node (ref "H15") (pin "6") (pinfunction "6_6") (pintype "unspecified"))
      (node (ref "H5") (pin "6") (pinfunction "6_6") (pintype "unspecified"))
      (node (ref "R38") (pin "2") (pinfunction "2_2") (pintype "unspecified"))
    )
    (net (code "44") (name "Net-(H15-Pad7)") (class "Default")
      (node (ref "H15") (pin "7") (pinfunction "7_7") (pintype "unspecified"))
      (node (ref "H5") (pin "7") (pinfunction "7_7") (pintype "unspecified"))
      (node (ref "R39") (pin "2") (pinfunction "2_2") (pintype "unspecified"))
    )
    (net (code "45") (name "Net-(H15-Pad8)") (class "Default")
      (node (ref "H15") (pin "8") (pinfunction "8_8") (pintype "unspecified"))
      (node (ref "H5") (pin "8") (pinfunction "8_8") (pintype "unspecified"))
      (node (ref "R40") (pin "2") (pinfunction "2_2") (pintype "unspecified"))
    )
    (net (code "46") (name "Net-(H16-Pad1)") (class "Default")
      (node (ref "H16") (pin "1") (pinfunction "1_1") (pintype "unspecified"))
      (node (ref "H6") (pin "1") (pinfunction "1_1") (pintype "unspecified"))
      (node (ref "R41") (pin "2") (pinfunction "2_2") (pintype "unspecified"))
    )
    (net (code "47") (name "Net-(H16-Pad2)") (class "Default")
      (node (ref "H16") (pin "2") (pinfunction "2_2") (pintype "unspecified"))
      (node (ref "H6") (pin "2") (pinfunction "2_2") (pintype "unspecified"))
      (node (ref "R42") (pin "2") (pinfunction "2_2") (pintype "unspecified"))
    )
    (net (code "48") (name "Net-(H16-Pad3)") (class "Default")
      (node (ref "H16") (pin "3") (pinfunction "3_3") (pintype "unspecified"))
      (node (ref "H6") (pin "3") (pinfunction "3_3") (pintype "unspecified"))
      (node (ref "R43") (pin "2") (pinfunction "2_2") (pintype "unspecified"))
    )
    (net (code "49") (name "Net-(H16-Pad4)") (class "Default")
      (node (ref "H16") (pin "4") (pinfunction "4_4") (pintype "unspecified"))
      (node (ref "H6") (pin "4") (pinfunction "4_4") (pintype "unspecified"))
      (node (ref "R44") (pin "2") (pinfunction "2_2") (pintype "unspecified"))
    )
    (net (code "50") (name "Net-(H16-Pad5)") (class "Default")
      (node (ref "H16") (pin "5") (pinfunction "5_5") (pintype "unspecified"))
      (node (ref "H6") (pin "5") (pinfunction "5_5") (pintype "unspecified"))
      (node (ref "R45") (pin "2") (pinfunction "2_2") (pintype "unspecified"))
    )
    (net (code "51") (name "Net-(H16-Pad6)") (class "Default")
      (node (ref "H16") (pin "6") (pinfunction "6_6") (pintype "unspecified"))
      (node (ref "H6") (pin "6") (pinfunction "6_6") (pintype "unspecified"))
      (node (ref "R46") (pin "2") (pinfunction "2_2") (pintype "unspecified"))
    )
    (net (code "52") (name "Net-(H16-Pad7)") (class "Default")
      (node (ref "H16") (pin "7") (pinfunction "7_7") (pintype "unspecified"))
      (node (ref "H6") (pin "7") (pinfunction "7_7") (pintype "unspecified"))
      (node (ref "R47") (pin "2") (pinfunction "2_2") (pintype "unspecified"))
    )
    (net (code "53") (name "Net-(H16-Pad8)") (class "Default")
      (node (ref "H16") (pin "8") (pinfunction "8_8") (pintype "unspecified"))
      (node (ref "H6") (pin "8") (pinfunction "8_8") (pintype "unspecified"))
      (node (ref "R48") (pin "2") (pinfunction "2_2") (pintype "unspecified"))
    )
    (net (code "54") (name "Net-(H17-Pad1)") (class "Default")
      (node (ref "H17") (pin "1") (pinfunction "1_1") (pintype "unspecified"))
      (node (ref "H7") (pin "1") (pinfunction "1_1") (pintype "unspecified"))
      (node (ref "R49") (pin "2") (pinfunction "2_2") (pintype "unspecified"))
    )
    (net (code "55") (name "Net-(H17-Pad2)") (class "Default")
      (node (ref "H17") (pin "2") (pinfunction "2_2") (pintype "unspecified"))
      (node (ref "H7") (pin "2") (pinfunction "2_2") (pintype "unspecified"))
      (node (ref "R50") (pin "2") (pinfunction "2_2") (pintype "unspecified"))
    )
    (net (code "56") (name "Net-(H17-Pad3)") (class "Default")
      (node (ref "H17") (pin "3") (pinfunction "3_3") (pintype "unspecified"))
      (node (ref "H7") (pin "3") (pinfunction "3_3") (pintype "unspecified"))
      (node (ref "R51") (pin "2") (pinfunction "2_2") (pintype "unspecified"))
    )
    (net (code "57") (name "Net-(H17-Pad4)") (class "Default")
      (node (ref "H17") (pin "4") (pinfunction "4_4") (pintype "unspecified"))
      (node (ref "H7") (pin "4") (pinfunction "4_4") (pintype "unspecified"))
      (node (ref "R52") (pin "2") (pinfunction "2_2") (pintype "unspecified"))
    )
    (net (code "58") (name "Net-(H17-Pad5)") (class "Default")
      (node (ref "H17") (pin "5") (pinfunction "5_5") (pintype "unspecified"))
      (node (ref "H7") (pin "5") (pinfunction "5_5") (pintype "unspecified"))
      (node (ref "R53") (pin "2") (pinfunction "2_2") (pintype "unspecified"))
    )
    (net (code "59") (name "Net-(H17-Pad6)") (class "Default")
      (node (ref "H17") (pin "6") (pinfunction "6_6") (pintype "unspecified"))
      (node (ref "H7") (pin "6") (pinfunction "6_6") (pintype "unspecified"))
      (node (ref "R54") (pin "2") (pinfunction "2_2") (pintype "unspecified"))
    )
    (net (code "60") (name "Net-(H17-Pad7)") (class "Default")
      (node (ref "H17") (pin "7") (pinfunction "7_7") (pintype "unspecified"))
      (node (ref "H7") (pin "7") (pinfunction "7_7") (pintype "unspecified"))
      (node (ref "R55") (pin "2") (pinfunction "2_2") (pintype "unspecified"))
    )
    (net (code "61") (name "Net-(H17-Pad8)") (class "Default")
      (node (ref "H17") (pin "8") (pinfunction "8_8") (pintype "unspecified"))
      (node (ref "H7") (pin "8") (pinfunction "8_8") (pintype "unspecified"))
      (node (ref "R56") (pin "2") (pinfunction "2_2") (pintype "unspecified"))
    )
    (net (code "62") (name "Net-(H18-Pad1)") (class "Default")
      (node (ref "H18") (pin "1") (pinfunction "1_1") (pintype "unspecified"))
      (node (ref "H8") (pin "1") (pinfunction "1_1") (pintype "unspecified"))
      (node (ref "R57") (pin "2") (pinfunction "2_2") (pintype "unspecified"))
    )
    (net (code "63") (name "Net-(H18-Pad2)") (class "Default")
      (node (ref "H18") (pin "2") (pinfunction "2_2") (pintype "unspecified"))
      (node (ref "H8") (pin "2") (pinfunction "2_2") (pintype "unspecified"))
      (node (ref "R58") (pin "2") (pinfunction "2_2") (pintype "unspecified"))
    )
    (net (code "64") (name "Net-(H18-Pad3)") (class "Default")
      (node (ref "H18") (pin "3") (pinfunction "3_3") (pintype "unspecified"))
      (node (ref "H8") (pin "3") (pinfunction "3_3") (pintype "unspecified"))
      (node (ref "R59") (pin "2") (pinfunction "2_2") (pintype "unspecified"))
    )
    (net (code "65") (name "Net-(H18-Pad4)") (class "Default")
      (node (ref "H18") (pin "4") (pinfunction "4_4") (pintype "unspecified"))
      (node (ref "H8") (pin "4") (pinfunction "4_4") (pintype "unspecified"))
      (node (ref "R60") (pin "2") (pinfunction "2_2") (pintype "unspecified"))
    )
    (net (code "66") (name "Net-(H18-Pad5)") (class "Default")
      (node (ref "H18") (pin "5") (pinfunction "5_5") (pintype "unspecified"))
      (node (ref "H8") (pin "5") (pinfunction "5_5") (pintype "unspecified"))
      (node (ref "R61") (pin "2") (pinfunction "2_2") (pintype "unspecified"))
    )
    (net (code "67") (name "Net-(H18-Pad6)") (class "Default")
      (node (ref "H18") (pin "6") (pinfunction "6_6") (pintype "unspecified"))
      (node (ref "H8") (pin "6") (pinfunction "6_6") (pintype "unspecified"))
      (node (ref "R62") (pin "2") (pinfunction "2_2") (pintype "unspecified"))
    )
    (net (code "68") (name "Net-(H18-Pad7)") (class "Default")
      (node (ref "H18") (pin "7") (pinfunction "7_7") (pintype "unspecified"))
      (node (ref "H8") (pin "7") (pinfunction "7_7") (pintype "unspecified"))
      (node (ref "R63") (pin "2") (pinfunction "2_2") (pintype "unspecified"))
    )
    (net (code "69") (name "Net-(H18-Pad8)") (class "Default")
      (node (ref "H18") (pin "8") (pinfunction "8_8") (pintype "unspecified"))
      (node (ref "H8") (pin "8") (pinfunction "8_8") (pintype "unspecified"))
      (node (ref "R64") (pin "2") (pinfunction "2_2") (pintype "unspecified"))
    )
    (net (code "70") (name "Net-(H19-Pad1)") (class "Default")
      (node (ref "H19") (pin "1") (pinfunction "1_1") (pintype "unspecified"))
      (node (ref "H9") (pin "1") (pinfunction "1_1") (pintype "unspecified"))
      (node (ref "T1") (pin "C") (pinfunction "C_C") (pintype "bidirectional"))
      (node (ref "T2") (pin "C") (pinfunction "C_C") (pintype "bidirectional"))
    )
    (net (code "71") (name "Net-(H19-Pad2)") (class "Default")
      (node (ref "H19") (pin "2") (pinfunction "2_2") (pintype "unspecified"))
      (node (ref "H9") (pin "2") (pinfunction "2_2") (pintype "unspecified"))
      (node (ref "T3") (pin "C") (pinfunction "C_C") (pintype "bidirectional"))
      (node (ref "T4") (pin "C") (pinfunction "C_C") (pintype "bidirectional"))
    )
    (net (code "72") (name "Net-(H19-Pad3)") (class "Default")
      (node (ref "H19") (pin "3") (pinfunction "3_3") (pintype "unspecified"))
      (node (ref "H9") (pin "3") (pinfunction "3_3") (pintype "unspecified"))
      (node (ref "T5") (pin "C") (pinfunction "C_C") (pintype "bidirectional"))
      (node (ref "T6") (pin "C") (pinfunction "C_C") (pintype "bidirectional"))
    )
    (net (code "73") (name "Net-(H19-Pad4)") (class "Default")
      (node (ref "H19") (pin "4") (pinfunction "4_4") (pintype "unspecified"))
      (node (ref "H9") (pin "4") (pinfunction "4_4") (pintype "unspecified"))
      (node (ref "T7") (pin "C") (pinfunction "C_C") (pintype "bidirectional"))
      (node (ref "T8") (pin "C") (pinfunction "C_C") (pintype "bidirectional"))
    )
    (net (code "74") (name "Net-(H19-Pad5)") (class "Default")
      (node (ref "H19") (pin "5") (pinfunction "5_5") (pintype "unspecified"))
      (node (ref "H9") (pin "5") (pinfunction "5_5") (pintype "unspecified"))
      (node (ref "T10") (pin "C") (pinfunction "C_C") (pintype "bidirectional"))
      (node (ref "T9") (pin "C") (pinfunction "C_C") (pintype "bidirectional"))
    )
    (net (code "75") (name "Net-(H19-Pad6)") (class "Default")
      (node (ref "H19") (pin "6") (pinfunction "6_6") (pintype "unspecified"))
      (node (ref "H9") (pin "6") (pinfunction "6_6") (pintype "unspecified"))
      (node (ref "T11") (pin "C") (pinfunction "C_C") (pintype "bidirectional"))
      (node (ref "T12") (pin "C") (pinfunction "C_C") (pintype "bidirectional"))
    )
    (net (code "76") (name "Net-(H19-Pad7)") (class "Default")
      (node (ref "H19") (pin "7") (pinfunction "7_7") (pintype "unspecified"))
      (node (ref "H9") (pin "7") (pinfunction "7_7") (pintype "unspecified"))
      (node (ref "T13") (pin "C") (pinfunction "C_C") (pintype "bidirectional"))
      (node (ref "T14") (pin "C") (pinfunction "C_C") (pintype "bidirectional"))
    )
    (net (code "77") (name "Net-(H19-Pad8)") (class "Default")
      (node (ref "H19") (pin "8") (pinfunction "8_8") (pintype "unspecified"))
      (node (ref "H9") (pin "8") (pinfunction "8_8") (pintype "unspecified"))
      (node (ref "T15") (pin "C") (pinfunction "C_C") (pintype "bidirectional"))
      (node (ref "T16") (pin "C") (pinfunction "C_C") (pintype "bidirectional"))
    )
    (net (code "78") (name "Net-(H20-Pad3)") (class "Default")
      (node (ref "H20") (pin "3") (pinfunction "3_3") (pintype "unspecified"))
      (node (ref "U1") (pin "3") (pinfunction "RESET_3") (pintype "unspecified"))
    )
    (net (code "79") (name "Net-(H20-Pad4)") (class "Default")
      (node (ref "H20") (pin "4") (pinfunction "4_4") (pintype "unspecified"))
      (node (ref "U1") (pin "4") (pinfunction "GND_4") (pintype "unspecified"))
    )
    (net (code "80") (name "Net-(H21-Pad13)") (class "Default")
      (node (ref "H21") (pin "13") (pinfunction "13_13") (pintype "unspecified"))
      (node (ref "U1") (pin "28") (pinfunction "RESET_28") (pintype "unspecified"))
    )
    (net (code "81") (name "Net-(IC1-QA)") (class "Default")
      (node (ref "IC1") (pin "15") (pinfunction "QA_15") (pintype "bidirectional"))
      (node (ref "R1") (pin "1") (pinfunction "1_1") (pintype "unspecified"))
    )
    (net (code "82") (name "Net-(IC1-QB)") (class "Default")
      (node (ref "IC1") (pin "1") (pinfunction "QB_1") (pintype "bidirectional"))
      (node (ref "R2") (pin "1") (pinfunction "1_1") (pintype "unspecified"))
    )
    (net (code "83") (name "Net-(IC1-QC)") (class "Default")
      (node (ref "IC1") (pin "2") (pinfunction "QC_2") (pintype "bidirectional"))
      (node (ref "R3") (pin "1") (pinfunction "1_1") (pintype "unspecified"))
    )
    (net (code "84") (name "Net-(IC1-QD)") (class "Default")
      (node (ref "IC1") (pin "3") (pinfunction "QD_3") (pintype "bidirectional"))
      (node (ref "R4") (pin "1") (pinfunction "1_1") (pintype "unspecified"))
    )
    (net (code "85") (name "Net-(IC1-QE)") (class "Default")
      (node (ref "IC1") (pin "4") (pinfunction "QE_4") (pintype "bidirectional"))
      (node (ref "R5") (pin "1") (pinfunction "1_1") (pintype "unspecified"))
    )
    (net (code "86") (name "Net-(IC1-QF)") (class "Default")
      (node (ref "IC1") (pin "5") (pinfunction "QF_5") (pintype "bidirectional"))
      (node (ref "R6") (pin "1") (pinfunction "1_1") (pintype "unspecified"))
    )
    (net (code "87") (name "Net-(IC1-QG)") (class "Default")
      (node (ref "IC1") (pin "6") (pinfunction "QG_6") (pintype "bidirectional"))
      (node (ref "R7") (pin "1") (pinfunction "1_1") (pintype "unspecified"))
    )
    (net (code "88") (name "Net-(IC1-QH)") (class "Default")
      (node (ref "IC1") (pin "7") (pinfunction "QH_7") (pintype "bidirectional"))
      (node (ref "R8") (pin "1") (pinfunction "1_1") (pintype "unspecified"))
    )
    (net (code "89") (name "Net-(IC1-QH*)") (class "Default")
      (node (ref "IC1") (pin "9") (pinfunction "QH*_9") (pintype "bidirectional"))
      (node (ref "IC2") (pin "14") (pinfunction "SER_14") (pintype "bidirectional"))
    )
    (net (code "90") (name "Net-(IC1-RCK)") (class "Default")
      (node (ref "H20") (pin "13") (pinfunction "13_13") (pintype "unspecified"))
      (node (ref "IC1") (pin "12") (pinfunction "RCK_12") (pintype "bidirectional"))
      (node (ref "IC2") (pin "12") (pinfunction "RCK_12") (pintype "bidirectional"))
      (node (ref "IC3") (pin "12") (pinfunction "RCK_12") (pintype "bidirectional"))
      (node (ref "IC4") (pin "12") (pinfunction "RCK_12") (pintype "bidirectional"))
      (node (ref "IC5") (pin "12") (pinfunction "RCK_12") (pintype "bidirectional"))
      (node (ref "IC6") (pin "12") (pinfunction "RCK_12") (pintype "bidirectional"))
      (node (ref "IC7") (pin "12") (pinfunction "RCK_12") (pintype "bidirectional"))
      (node (ref "IC8") (pin "12") (pinfunction "RCK_12") (pintype "bidirectional"))
      (node (ref "IC9") (pin "12") (pinfunction "RCK_12") (pintype "bidirectional"))
      (node (ref "U1") (pin "13") (pinfunction "D10_13") (pintype "unspecified"))
    )
    (net (code "91") (name "Net-(IC1-SCK)") (class "Default")
      (node (ref "H21") (pin "1") (pinfunction "1_1") (pintype "unspecified"))
      (node (ref "IC1") (pin "11") (pinfunction "SCK_11") (pintype "bidirectional"))
      (node (ref "IC2") (pin "11") (pinfunction "SCK_11") (pintype "bidirectional"))
      (node (ref "IC3") (pin "11") (pinfunction "SCK_11") (pintype "bidirectional"))
      (node (ref "IC4") (pin "11") (pinfunction "SCK_11") (pintype "bidirectional"))
      (node (ref "IC5") (pin "11") (pinfunction "SCK_11") (pintype "bidirectional"))
      (node (ref "IC6") (pin "11") (pinfunction "SCK_11") (pintype "bidirectional"))
      (node (ref "IC7") (pin "11") (pinfunction "SCK_11") (pintype "bidirectional"))
      (node (ref "IC8") (pin "11") (pinfunction "SCK_11") (pintype "bidirectional"))
      (node (ref "IC9") (pin "11") (pinfunction "SCK_11") (pintype "bidirectional"))
      (node (ref "U1") (pin "16") (pinfunction "D13/SCK_16") (pintype "unspecified"))
    )
    (net (code "92") (name "Net-(IC1-SER)") (class "Default")
      (node (ref "H20") (pin "14") (pinfunction "14_14") (pintype "unspecified"))
      (node (ref "IC1") (pin "14") (pinfunction "SER_14") (pintype "bidirectional"))
      (node (ref "U1") (pin "14") (pinfunction "D11/MOSI_14") (pintype "unspecified"))
    )
    (net (code "93") (name "Net-(IC2-QA)") (class "Default")
      (node (ref "IC2") (pin "15") (pinfunction "QA_15") (pintype "bidirectional"))
      (node (ref "R9") (pin "1") (pinfunction "1_1") (pintype "unspecified"))
    )
    (net (code "94") (name "Net-(IC2-QB)") (class "Default")
      (node (ref "IC2") (pin "1") (pinfunction "QB_1") (pintype "bidirectional"))
      (node (ref "R10") (pin "1") (pinfunction "1_1") (pintype "unspecified"))
    )
    (net (code "95") (name "Net-(IC2-QC)") (class "Default")
      (node (ref "IC2") (pin "2") (pinfunction "QC_2") (pintype "bidirectional"))
      (node (ref "R11") (pin "1") (pinfunction "1_1") (pintype "unspecified"))
    )
    (net (code "96") (name "Net-(IC2-QD)") (class "Default")
      (node (ref "IC2") (pin "3") (pinfunction "QD_3") (pintype "bidirectional"))
      (node (ref "R12") (pin "1") (pinfunction "1_1") (pintype "unspecified"))
    )
    (net (code "97") (name "Net-(IC2-QE)") (class "Default")
      (node (ref "IC2") (pin "4") (pinfunction "QE_4") (pintype "bidirectional"))
      (node (ref "R13") (pin "1") (pinfunction "1_1") (pintype "unspecified"))
    )
    (net (code "98") (name "Net-(IC2-QF)") (class "Default")
      (node (ref "IC2") (pin "5") (pinfunction "QF_5") (pintype "bidirectional"))
      (node (ref "R14") (pin "1") (pinfunction "1_1") (pintype "unspecified"))
    )
    (net (code "99") (name "Net-(IC2-QG)") (class "Default")
      (node (ref "IC2") (pin "6") (pinfunction "QG_6") (pintype "bidirectional"))
      (node (ref "R15") (pin "1") (pinfunction "1_1") (pintype "unspecified"))
    )
    (net (code "100") (name "Net-(IC2-QH)") (class "Default")
      (node (ref "IC2") (pin "7") (pinfunction "QH_7") (pintype "bidirectional"))
      (node (ref "R16") (pin "1") (pinfunction "1_1") (pintype "unspecified"))
    )
    (net (code "101") (name "Net-(IC2-QH*)") (class "Default")
      (node (ref "IC2") (pin "9") (pinfunction "QH*_9") (pintype "bidirectional"))
      (node (ref "IC3") (pin "14") (pinfunction "SER_14") (pintype "bidirectional"))
    )
    (net (code "102") (name "Net-(IC3-QA)") (class "Default")
      (node (ref "IC3") (pin "15") (pinfunction "QA_15") (pintype "bidirectional"))
      (node (ref "R17") (pin "1") (pinfunction "1_1") (pintype "unspecified"))
    )
    (net (code "103") (name "Net-(IC3-QB)") (class "Default")
      (node (ref "IC3") (pin "1") (pinfunction "QB_1") (pintype "bidirectional"))
      (node (ref "R18") (pin "1") (pinfunction "1_1") (pintype "unspecified"))
    )
    (net (code "104") (name "Net-(IC3-QC)") (class "Default")
      (node (ref "IC3") (pin "2") (pinfunction "QC_2") (pintype "bidirectional"))
      (node (ref "R19") (pin "1") (pinfunction "1_1") (pintype "unspecified"))
    )
    (net (code "105") (name "Net-(IC3-QD)") (class "Default")
      (node (ref "IC3") (pin "3") (pinfunction "QD_3") (pintype "bidirectional"))
      (node (ref "R20") (pin "1") (pinfunction "1_1") (pintype "unspecified"))
    )
    (net (code "106") (name "Net-(IC3-QE)") (class "Default")
      (node (ref "IC3") (pin "4") (pinfunction "QE_4") (pintype "bidirectional"))
      (node (ref "R21") (pin "1") (pinfunction "1_1") (pintype "unspecified"))
    )
    (net (code "107") (name "Net-(IC3-QF)") (class "Default")
      (node (ref "IC3") (pin "5") (pinfunction "QF_5") (pintype "bidirectional"))
      (node (ref "R22") (pin "1") (pinfunction "1_1") (pintype "unspecified"))
    )
    (net (code "108") (name "Net-(IC3-QG)") (class "Default")
      (node (ref "IC3") (pin "6") (pinfunction "QG_6") (pintype "bidirectional"))
      (node (ref "R23") (pin "1") (pinfunction "1_1") (pintype "unspecified"))
    )
    (net (code "109") (name "Net-(IC3-QH)") (class "Default")
      (node (ref "IC3") (pin "7") (pinfunction "QH_7") (pintype "bidirectional"))
      (node (ref "R24") (pin "1") (pinfunction "1_1") (pintype "unspecified"))
    )
    (net (code "110") (name "Net-(IC3-QH*)") (class "Default")
      (node (ref "IC3") (pin "9") (pinfunction "QH*_9") (pintype "bidirectional"))
      (node (ref "IC4") (pin "14") (pinfunction "SER_14") (pintype "bidirectional"))
    )
    (net (code "111") (name "Net-(IC4-QA)") (class "Default")
      (node (ref "IC4") (pin "15") (pinfunction "QA_15") (pintype "bidirectional"))
      (node (ref "R25") (pin "1") (pinfunction "1_1") (pintype "unspecified"))
    )
    (net (code "112") (name "Net-(IC4-QB)") (class "Default")
      (node (ref "IC4") (pin "1") (pinfunction "QB_1") (pintype "bidirectional"))
      (node (ref "R26") (pin "1") (pinfunction "1_1") (pintype "unspecified"))
    )
    (net (code "113") (name "Net-(IC4-QC)") (class "Default")
      (node (ref "IC4") (pin "2") (pinfunction "QC_2") (pintype "bidirectional"))
      (node (ref "R27") (pin "1") (pinfunction "1_1") (pintype "unspecified"))
    )
    (net (code "114") (name "Net-(IC4-QD)") (class "Default")
      (node (ref "IC4") (pin "3") (pinfunction "QD_3") (pintype "bidirectional"))
      (node (ref "R28") (pin "1") (pinfunction "1_1") (pintype "unspecified"))
    )
    (net (code "115") (name "Net-(IC4-QE)") (class "Default")
      (node (ref "IC4") (pin "4") (pinfunction "QE_4") (pintype "bidirectional"))
      (node (ref "R29") (pin "1") (pinfunction "1_1") (pintype "unspecified"))
    )
    (net (code "116") (name "Net-(IC4-QF)") (class "Default")
      (node (ref "IC4") (pin "5") (pinfunction "QF_5") (pintype "bidirectional"))
      (node (ref "R30") (pin "1") (pinfunction "1_1") (pintype "unspecified"))
    )
    (net (code "117") (name "Net-(IC4-QG)") (class "Default")
      (node (ref "IC4") (pin "6") (pinfunction "QG_6") (pintype "bidirectional"))
      (node (ref "R31") (pin "1") (pinfunction "1_1") (pintype "unspecified"))
    )
    (net (code "118") (name "Net-(IC4-QH)") (class "Default")
      (node (ref "IC4") (pin "7") (pinfunction "QH_7") (pintype "bidirectional"))
      (node (ref "R32") (pin "1") (pinfunction "1_1") (pintype "unspecified"))
    )
    (net (code "119") (name "Net-(IC4-QH*)") (class "Default")
      (node (ref "IC4") (pin "9") (pinfunction "QH*_9") (pintype "bidirectional"))
      (node (ref "IC5") (pin "14") (pinfunction "SER_14") (pintype "bidirectional"))
    )
    (net (code "120") (name "Net-(IC5-QA)") (class "Default")
      (node (ref "IC5") (pin "15") (pinfunction "QA_15") (pintype "bidirectional"))
      (node (ref "R33") (pin "1") (pinfunction "1_1") (pintype "unspecified"))
    )
    (net (code "121") (name "Net-(IC5-QB)") (class "Default")
      (node (ref "IC5") (pin "1") (pinfunction "QB_1") (pintype "bidirectional"))
      (node (ref "R34") (pin "1") (pinfunction "1_1") (pintype "unspecified"))
    )
    (net (code "122") (name "Net-(IC5-QC)") (class "Default")
      (node (ref "IC5") (pin "2") (pinfunction "QC_2") (pintype "bidirectional"))
      (node (ref "R35") (pin "1") (pinfunction "1_1") (pintype "unspecified"))
    )
    (net (code "123") (name "Net-(IC5-QD)") (class "Default")
      (node (ref "IC5") (pin "3") (pinfunction "QD_3") (pintype "bidirectional"))
      (node (ref "R36") (pin "1") (pinfunction "1_1") (pintype "unspecified"))
    )
    (net (code "124") (name "Net-(IC5-QE)") (class "Default")
      (node (ref "IC5") (pin "4") (pinfunction "QE_4") (pintype "bidirectional"))
      (node (ref "R37") (pin "1") (pinfunction "1_1") (pintype "unspecified"))
    )
    (net (code "125") (name "Net-(IC5-QF)") (class "Default")
      (node (ref "IC5") (pin "5") (pinfunction "QF_5") (pintype "bidirectional"))
      (node (ref "R38") (pin "1") (pinfunction "1_1") (pintype "unspecified"))
    )
    (net (code "126") (name "Net-(IC5-QG)") (class "Default")
      (node (ref "IC5") (pin "6") (pinfunction "QG_6") (pintype "bidirectional"))
      (node (ref "R39") (pin "1") (pinfunction "1_1") (pintype "unspecified"))
    )
    (net (code "127") (name "Net-(IC5-QH)") (class "Default")
      (node (ref "IC5") (pin "7") (pinfunction "QH_7") (pintype "bidirectional"))
      (node (ref "R40") (pin "1") (pinfunction "1_1") (pintype "unspecified"))
    )
    (net (code "128") (name "Net-(IC5-QH*)") (class "Default")
      (node (ref "IC5") (pin "9") (pinfunction "QH*_9") (pintype "bidirectional"))
      (node (ref "IC6") (pin "14") (pinfunction "SER_14") (pintype "bidirectional"))
    )
    (net (code "129") (name "Net-(IC6-QA)") (class "Default")
      (node (ref "IC6") (pin "15") (pinfunction "QA_15") (pintype "bidirectional"))
      (node (ref "R41") (pin "1") (pinfunction "1_1") (pintype "unspecified"))
    )
    (net (code "130") (name "Net-(IC6-QB)") (class "Default")
      (node (ref "IC6") (pin "1") (pinfunction "QB_1") (pintype "bidirectional"))
      (node (ref "R42") (pin "1") (pinfunction "1_1") (pintype "unspecified"))
    )
    (net (code "131") (name "Net-(IC6-QC)") (class "Default")
      (node (ref "IC6") (pin "2") (pinfunction "QC_2") (pintype "bidirectional"))
      (node (ref "R43") (pin "1") (pinfunction "1_1") (pintype "unspecified"))
    )
    (net (code "132") (name "Net-(IC6-QD)") (class "Default")
      (node (ref "IC6") (pin "3") (pinfunction "QD_3") (pintype "bidirectional"))
      (node (ref "R44") (pin "1") (pinfunction "1_1") (pintype "unspecified"))
    )
    (net (code "133") (name "Net-(IC6-QE)") (class "Default")
      (node (ref "IC6") (pin "4") (pinfunction "QE_4") (pintype "bidirectional"))
      (node (ref "R45") (pin "1") (pinfunction "1_1") (pintype "unspecified"))
    )
    (net (code "134") (name "Net-(IC6-QF)") (class "Default")
      (node (ref "IC6") (pin "5") (pinfunction "QF_5") (pintype "bidirectional"))
      (node (ref "R46") (pin "1") (pinfunction "1_1") (pintype "unspecified"))
    )
    (net (code "135") (name "Net-(IC6-QG)") (class "Default")
      (node (ref "IC6") (pin "6") (pinfunction "QG_6") (pintype "bidirectional"))
      (node (ref "R47") (pin "1") (pinfunction "1_1") (pintype "unspecified"))
    )
    (net (code "136") (name "Net-(IC6-QH)") (class "Default")
      (node (ref "IC6") (pin "7") (pinfunction "QH_7") (pintype "bidirectional"))
      (node (ref "R48") (pin "1") (pinfunction "1_1") (pintype "unspecified"))
    )
    (net (code "137") (name "Net-(IC6-QH*)") (class "Default")
      (node (ref "IC6") (pin "9") (pinfunction "QH*_9") (pintype "bidirectional"))
      (node (ref "IC7") (pin "14") (pinfunction "SER_14") (pintype "bidirectional"))
    )
    (net (code "138") (name "Net-(IC7-QA)") (class "Default")
      (node (ref "IC7") (pin "15") (pinfunction "QA_15") (pintype "bidirectional"))
      (node (ref "R49") (pin "1") (pinfunction "1_1") (pintype "unspecified"))
    )
    (net (code "139") (name "Net-(IC7-QB)") (class "Default")
      (node (ref "IC7") (pin "1") (pinfunction "QB_1") (pintype "bidirectional"))
      (node (ref "R50") (pin "1") (pinfunction "1_1") (pintype "unspecified"))
    )
    (net (code "140") (name "Net-(IC7-QC)") (class "Default")
      (node (ref "IC7") (pin "2") (pinfunction "QC_2") (pintype "bidirectional"))
      (node (ref "R51") (pin "1") (pinfunction "1_1") (pintype "unspecified"))
    )
    (net (code "141") (name "Net-(IC7-QD)") (class "Default")
      (node (ref "IC7") (pin "3") (pinfunction "QD_3") (pintype "bidirectional"))
      (node (ref "R52") (pin "1") (pinfunction "1_1") (pintype "unspecified"))
    )
    (net (code "142") (name "Net-(IC7-QE)") (class "Default")
      (node (ref "IC7") (pin "4") (pinfunction "QE_4") (pintype "bidirectional"))
      (node (ref "R53") (pin "1") (pinfunction "1_1") (pintype "unspecified"))
    )
    (net (code "143") (name "Net-(IC7-QF)") (class "Default")
      (node (ref "IC7") (pin "5") (pinfunction "QF_5") (pintype "bidirectional"))
      (node (ref "R54") (pin "1") (pinfunction "1_1") (pintype "unspecified"))
    )
    (net (code "144") (name "Net-(IC7-QG)") (class "Default")
      (node (ref "IC7") (pin "6") (pinfunction "QG_6") (pintype "bidirectional"))
      (node (ref "R55") (pin "1") (pinfunction "1_1") (pintype "unspecified"))
    )
    (net (code "145") (name "Net-(IC7-QH)") (class "Default")
      (node (ref "IC7") (pin "7") (pinfunction "QH_7") (pintype "bidirectional"))
      (node (ref "R56") (pin "1") (pinfunction "1_1") (pintype "unspecified"))
    )
    (net (code "146") (name "Net-(IC7-QH*)") (class "Default")
      (node (ref "IC7") (pin "9") (pinfunction "QH*_9") (pintype "bidirectional"))
      (node (ref "IC8") (pin "14") (pinfunction "SER_14") (pintype "bidirectional"))
    )
    (net (code "147") (name "Net-(IC8-QA)") (class "Default")
      (node (ref "IC8") (pin "15") (pinfunction "QA_15") (pintype "bidirectional"))
      (node (ref "R57") (pin "1") (pinfunction "1_1") (pintype "unspecified"))
    )
    (net (code "148") (name "Net-(IC8-QB)") (class "Default")
      (node (ref "IC8") (pin "1") (pinfunction "QB_1") (pintype "bidirectional"))
      (node (ref "R58") (pin "1") (pinfunction "1_1") (pintype "unspecified"))
    )
    (net (code "149") (name "Net-(IC8-QC)") (class "Default")
      (node (ref "IC8") (pin "2") (pinfunction "QC_2") (pintype "bidirectional"))
      (node (ref "R59") (pin "1") (pinfunction "1_1") (pintype "unspecified"))
    )
    (net (code "150") (name "Net-(IC8-QD)") (class "Default")
      (node (ref "IC8") (pin "3") (pinfunction "QD_3") (pintype "bidirectional"))
      (node (ref "R60") (pin "1") (pinfunction "1_1") (pintype "unspecified"))
    )
    (net (code "151") (name "Net-(IC8-QE)") (class "Default")
      (node (ref "IC8") (pin "4") (pinfunction "QE_4") (pintype "bidirectional"))
      (node (ref "R61") (pin "1") (pinfunction "1_1") (pintype "unspecified"))
    )
    (net (code "152") (name "Net-(IC8-QF)") (class "Default")
      (node (ref "IC8") (pin "5") (pinfunction "QF_5") (pintype "bidirectional"))
      (node (ref "R62") (pin "1") (pinfunction "1_1") (pintype "unspecified"))
    )
    (net (code "153") (name "Net-(IC8-QG)") (class "Default")
      (node (ref "IC8") (pin "6") (pinfunction "QG_6") (pintype "bidirectional"))
      (node (ref "R63") (pin "1") (pinfunction "1_1") (pintype "unspecified"))
    )
    (net (code "154") (name "Net-(IC8-QH)") (class "Default")
      (node (ref "IC8") (pin "7") (pinfunction "QH_7") (pintype "bidirectional"))
      (node (ref "R64") (pin "1") (pinfunction "1_1") (pintype "unspecified"))
    )
    (net (code "155") (name "Net-(IC8-QH*)") (class "Default")
      (node (ref "IC8") (pin "9") (pinfunction "QH*_9") (pintype "bidirectional"))
      (node (ref "IC9") (pin "14") (pinfunction "SER_14") (pintype "bidirectional"))
    )
    (net (code "156") (name "Net-(IC9-QA)") (class "Default")
      (node (ref "IC9") (pin "15") (pinfunction "QA_15") (pintype "bidirectional"))
      (node (ref "T1") (pin "B") (pinfunction "B_B") (pintype "bidirectional"))
      (node (ref "T2") (pin "B") (pinfunction "B_B") (pintype "bidirectional"))
    )
    (net (code "157") (name "Net-(IC9-QB)") (class "Default")
      (node (ref "IC9") (pin "1") (pinfunction "QB_1") (pintype "bidirectional"))
      (node (ref "T3") (pin "B") (pinfunction "B_B") (pintype "bidirectional"))
      (node (ref "T4") (pin "B") (pinfunction "B_B") (pintype "bidirectional"))
    )
    (net (code "158") (name "Net-(IC9-QC)") (class "Default")
      (node (ref "IC9") (pin "2") (pinfunction "QC_2") (pintype "bidirectional"))
      (node (ref "T5") (pin "B") (pinfunction "B_B") (pintype "bidirectional"))
      (node (ref "T6") (pin "B") (pinfunction "B_B") (pintype "bidirectional"))
    )
    (net (code "159") (name "Net-(IC9-QD)") (class "Default")
      (node (ref "IC9") (pin "3") (pinfunction "QD_3") (pintype "bidirectional"))
      (node (ref "T7") (pin "B") (pinfunction "B_B") (pintype "bidirectional"))
      (node (ref "T8") (pin "B") (pinfunction "B_B") (pintype "bidirectional"))
    )
    (net (code "160") (name "Net-(IC9-QE)") (class "Default")
      (node (ref "IC9") (pin "4") (pinfunction "QE_4") (pintype "bidirectional"))
      (node (ref "T10") (pin "B") (pinfunction "B_B") (pintype "bidirectional"))
      (node (ref "T9") (pin "B") (pinfunction "B_B") (pintype "bidirectional"))
    )
    (net (code "161") (name "Net-(IC9-QF)") (class "Default")
      (node (ref "IC9") (pin "5") (pinfunction "QF_5") (pintype "bidirectional"))
      (node (ref "T11") (pin "B") (pinfunction "B_B") (pintype "bidirectional"))
      (node (ref "T12") (pin "B") (pinfunction "B_B") (pintype "bidirectional"))
    )
    (net (code "162") (name "Net-(IC9-QG)") (class "Default")
      (node (ref "IC9") (pin "6") (pinfunction "QG_6") (pintype "bidirectional"))
      (node (ref "T13") (pin "B") (pinfunction "B_B") (pintype "bidirectional"))
      (node (ref "T14") (pin "B") (pinfunction "B_B") (pintype "bidirectional"))
    )
    (net (code "163") (name "Net-(IC9-QH)") (class "Default")
      (node (ref "IC9") (pin "7") (pinfunction "QH_7") (pintype "bidirectional"))
      (node (ref "T15") (pin "B") (pinfunction "B_B") (pintype "bidirectional"))
      (node (ref "T16") (pin "B") (pinfunction "B_B") (pintype "bidirectional"))
    )
    (net (code "164") (name "Net-(U1-+5V)") (class "Default")
      (node (ref "H21") (pin "12") (pinfunction "12_12") (pintype "unspecified"))
      (node (ref "U1") (pin "27") (pinfunction "+5V_27") (pintype "unspecified"))
    )
    (net (code "165") (name "Net-(U1-3V3)") (class "Default")
      (node (ref "H21") (pin "2") (pinfunction "2_2") (pintype "unspecified"))
      (node (ref "U1") (pin "17") (pinfunction "3V3_17") (pintype "unspecified"))
    )
    (net (code "166") (name "Net-(U1-A0)") (class "Default")
      (node (ref "H21") (pin "4") (pinfunction "4_4") (pintype "unspecified"))
      (node (ref "U1") (pin "19") (pinfunction "A0_19") (pintype "unspecified"))
    )
    (net (code "167") (name "Net-(U1-A1)") (class "Default")
      (node (ref "H21") (pin "5") (pinfunction "5_5") (pintype "unspecified"))
      (node (ref "U1") (pin "20") (pinfunction "A1_20") (pintype "unspecified"))
    )
    (net (code "168") (name "Net-(U1-A2)") (class "Default")
      (node (ref "H21") (pin "6") (pinfunction "6_6") (pintype "unspecified"))
      (node (ref "U1") (pin "21") (pinfunction "A2_21") (pintype "unspecified"))
    )
    (net (code "169") (name "Net-(U1-A3)") (class "Default")
      (node (ref "H21") (pin "7") (pinfunction "7_7") (pintype "unspecified"))
      (node (ref "U1") (pin "22") (pinfunction "A3_22") (pintype "unspecified"))
    )
    (net (code "170") (name "Net-(U1-A4)") (class "Default")
      (node (ref "H21") (pin "8") (pinfunction "8_8") (pintype "unspecified"))
      (node (ref "U1") (pin "23") (pinfunction "A4_23") (pintype "unspecified"))
    )
    (net (code "171") (name "Net-(U1-A5)") (class "Default")
      (node (ref "H21") (pin "9") (pinfunction "9_9") (pintype "unspecified"))
      (node (ref "U1") (pin "24") (pinfunction "A5_24") (pintype "unspecified"))
    )
    (net (code "172") (name "Net-(U1-A6)") (class "Default")
      (node (ref "H21") (pin "10") (pinfunction "10_10") (pintype "unspecified"))
      (node (ref "U1") (pin "25") (pinfunction "A6_25") (pintype "unspecified"))
    )
    (net (code "173") (name "Net-(U1-A7)") (class "Default")
      (node (ref "H21") (pin "11") (pinfunction "11_11") (pintype "unspecified"))
      (node (ref "U1") (pin "26") (pinfunction "A7_26") (pintype "unspecified"))
    )
    (net (code "174") (name "Net-(U1-AREF)") (class "Default")
      (node (ref "H21") (pin "3") (pinfunction "3_3") (pintype "unspecified"))
      (node (ref "U1") (pin "18") (pinfunction "AREF_18") (pintype "unspecified"))
    )
    (net (code "175") (name "Net-(U1-D0{slash}RX)") (class "Default")
      (node (ref "H20") (pin "2") (pinfunction "2_2") (pintype "unspecified"))
      (node (ref "U1") (pin "2") (pinfunction "D0/RX_2") (pintype "unspecified"))
    )
    (net (code "176") (name "Net-(U1-D1{slash}TX)") (class "Default")
      (node (ref "H20") (pin "1") (pinfunction "1_1") (pintype "unspecified"))
      (node (ref "U1") (pin "1") (pinfunction "D1/TX_1") (pintype "unspecified"))
    )
    (net (code "177") (name "Net-(U1-D2)") (class "Default")
      (node (ref "H20") (pin "5") (pinfunction "5_5") (pintype "unspecified"))
      (node (ref "U1") (pin "5") (pinfunction "D2_5") (pintype "unspecified"))
    )
    (net (code "178") (name "Net-(U1-D3)") (class "Default")
      (node (ref "H20") (pin "6") (pinfunction "6_6") (pintype "unspecified"))
      (node (ref "U1") (pin "6") (pinfunction "D3_6") (pintype "unspecified"))
    )
    (net (code "179") (name "Net-(U1-D4)") (class "Default")
      (node (ref "H20") (pin "7") (pinfunction "7_7") (pintype "unspecified"))
      (node (ref "U1") (pin "7") (pinfunction "D4_7") (pintype "unspecified"))
    )
    (net (code "180") (name "Net-(U1-D6)") (class "Default")
      (node (ref "H20") (pin "9") (pinfunction "9_9") (pintype "unspecified"))
      (node (ref "U1") (pin "9") (pinfunction "D6_9") (pintype "unspecified"))
    )
    (net (code "181") (name "Net-(U1-D8)") (class "Default")
      (node (ref "H10") (pin "1") (pinfunction "1_1") (pintype "unspecified"))
      (node (ref "H20") (pin "11") (pinfunction "11_11") (pintype "unspecified"))
      (node (ref "U1") (pin "11") (pinfunction "D8_11") (pintype "unspecified"))
    )
    (net (code "182") (name "Net-(U1-D9)") (class "Default")
      (node (ref "H20") (pin "12") (pinfunction "12_12") (pintype "unspecified"))
      (node (ref "U1") (pin "12") (pinfunction "D9_12") (pintype "unspecified"))
    )
    (net (code "183") (name "Net-(U1-D12{slash}MISO)") (class "Default")
      (node (ref "H20") (pin "15") (pinfunction "15_15") (pintype "unspecified"))
      (node (ref "U1") (pin "15") (pinfunction "D12/MISO_15") (pintype "unspecified"))
    )
    (net (code "184") (name "unconnected-(IC9-QH*-Pad9)") (class "Default")
      (node (ref "IC9") (pin "9") (pinfunction "QH*_9") (pintype "bidirectional+no_connect"))
    )
  )
)
